# Y-babies_ATtiny84_v06.net
KiCad netlist of a schematic drawn in EAGLE
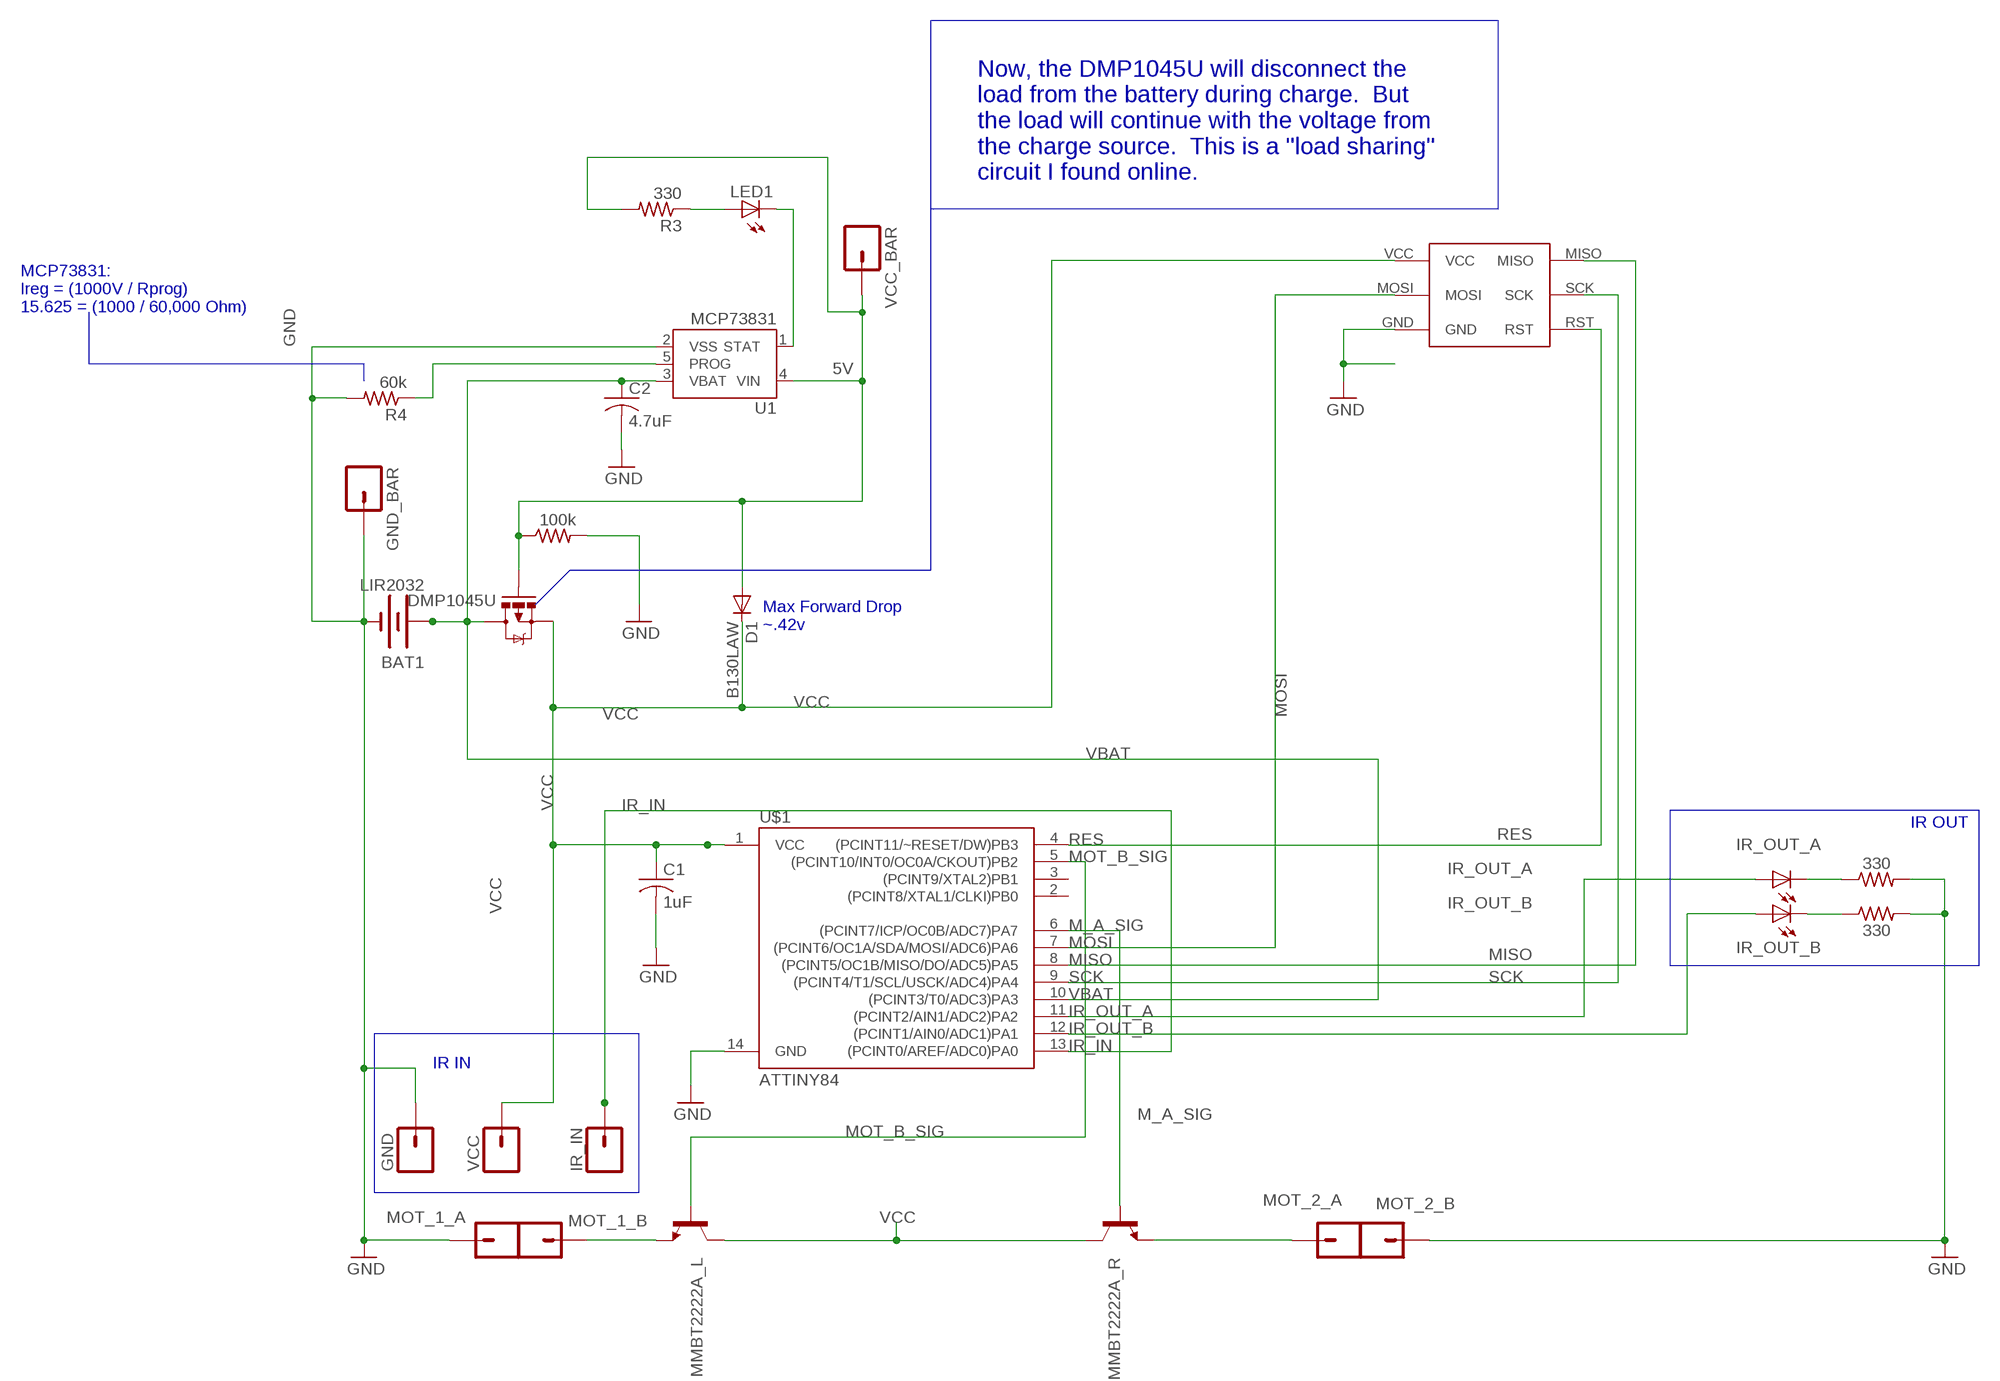
[diagram p0: schematic, sheet 1]

(export (version "E")
  (design (tool "Eeschema 10.0.6"))
  (components
    (comp (ref "BAT1")
      (value "LIR2032")
      (footprint "eagle-import:BATTCOM_20MM_PTH")
      (libsource (lib "eagle-import") (part "BATTERY20PTH"))
    )
    (comp (ref "C1")
      (value "1uF")
      (footprint "eagle-import:C0402K")
      (libsource (lib "eagle-import") (part "C-USC0402K"))
    )
    (comp (ref "C2")
      (value "4.7uF")
      (footprint "eagle-import:C0805K")
      (libsource (lib "eagle-import") (part "C-USC0805K"))
    )
    (comp (ref "D1")
      (value "B130LAW")
      (footprint "eagle-import:SOD123")
      (libsource (lib "eagle-import") (part "DIODE-SOD123"))
    )
    (comp (ref "DMP1045U")
      (value "MOSFET-PCHANNELSMD")
      (footprint "eagle-import:SOT23-3")
      (libsource (lib "eagle-import") (part "MOSFET-PCHANNELSMD"))
    )
    (comp (ref "GND")
      (value "M01PTH")
      (footprint "eagle-import:1X01")
      (libsource (lib "eagle-import") (part "M01PTH"))
    )
    (comp (ref "GND_BAR")
      (value "M01PTH")
      (footprint "eagle-import:1X01")
      (libsource (lib "eagle-import") (part "M01PTH"))
    )
    (comp (ref "IR_IN")
      (value "M01PTH")
      (footprint "eagle-import:1X01")
      (libsource (lib "eagle-import") (part "M01PTH"))
    )
    (comp (ref "IR_OUT_A")
      (value "LED3MM")
      (footprint "eagle-import:LED3MM")
      (libsource (lib "eagle-import") (part "LED3MM"))
    )
    (comp (ref "IR_OUT_B")
      (value "LED3MM")
      (footprint "eagle-import:LED3MM")
      (libsource (lib "eagle-import") (part "LED3MM"))
    )
    (comp (ref "LED1")
      (value "LEDSML0603")
      (footprint "eagle-import:SML0603")
      (libsource (lib "eagle-import") (part "LEDSML0603"))
    )
    (comp (ref "MMBT2222A_L")
      (value "TRANSISTOR_NPNSOT23")
      (footprint "eagle-import:SOT23")
      (libsource (lib "eagle-import") (part "TRANSISTOR_NPNSOT23"))
    )
    (comp (ref "MMBT2222A_R")
      (value "TRANSISTOR_NPNSOT23")
      (footprint "eagle-import:SOT23")
      (libsource (lib "eagle-import") (part "TRANSISTOR_NPNSOT23"))
    )
    (comp (ref "MOT_1_A")
      (value "M01SMD-4.5X1.5")
      (footprint "eagle-import:PAD-1.5X4.5")
      (libsource (lib "eagle-import") (part "M01SMD-4.5X1.5"))
    )
    (comp (ref "MOT_1_B")
      (value "M01SMD-4.5X1.5")
      (footprint "eagle-import:PAD-1.5X4.5")
      (libsource (lib "eagle-import") (part "M01SMD-4.5X1.5"))
    )
    (comp (ref "MOT_2_A")
      (value "M01SMD-4.5X1.5")
      (footprint "eagle-import:PAD-1.5X4.5")
      (libsource (lib "eagle-import") (part "M01SMD-4.5X1.5"))
    )
    (comp (ref "MOT_2_B")
      (value "M01SMD-4.5X1.5")
      (footprint "eagle-import:PAD-1.5X4.5")
      (libsource (lib "eagle-import") (part "M01SMD-4.5X1.5"))
    )
    (comp (ref "R1")
      (value "330")
      (footprint "eagle-import:R0402")
      (libsource (lib "eagle-import") (part "R-US_R0402"))
    )
    (comp (ref "R2")
      (value "330")
      (footprint "eagle-import:R0402")
      (libsource (lib "eagle-import") (part "R-US_R0402"))
    )
    (comp (ref "R3")
      (value "330")
      (footprint "eagle-import:R0402")
      (libsource (lib "eagle-import") (part "R-US_R0402"))
    )
    (comp (ref "R4")
      (value "60k")
      (footprint "eagle-import:R0402")
      (libsource (lib "eagle-import") (part "R-US_R0402"))
    )
    (comp (ref "R5")
      (value "100k")
      (footprint "eagle-import:R0402")
      (libsource (lib "eagle-import") (part "R-US_R0402"))
    )
    (comp (ref "U$1")
      (value "ATTINY84")
      (footprint "eagle-import:SO14")
      (libsource (lib "eagle-import") (part "ATTINY84"))
    )
    (comp (ref "U$2")
      (value "POGO_PIN_SPI_PAD")
      (footprint "eagle-import:POGO_PIN_SPI_PAD")
      (libsource (lib "eagle-import") (part "POGO_PIN_SPI_PAD"))
    )
    (comp (ref "U1")
      (value "MCP73831")
      (footprint "eagle-import:SOT23-5")
      (libsource (lib "eagle-import") (part "MCP73831"))
    )
    (comp (ref "VCC")
      (value "M01PTH")
      (footprint "eagle-import:1X01")
      (libsource (lib "eagle-import") (part "M01PTH"))
    )
    (comp (ref "VCC_BAR")
      (value "M01PTH")
      (footprint "eagle-import:1X01")
      (libsource (lib "eagle-import") (part "M01PTH"))
    )
  )
  (nets
    (net (code "1") (name "/5V") (class "Default")
      (node (ref "D1") (pin "A") (pinfunction "A_A") (pintype "passive"))
      (node (ref "DMP1045U") (pin "1") (pinfunction "G_1") (pintype "passive"))
      (node (ref "R3") (pin "2") (pinfunction "2_2") (pintype "passive"))
      (node (ref "R5") (pin "1") (pinfunction "1_1") (pintype "passive"))
      (node (ref "U1") (pin "4") (pinfunction "VIN_4") (pintype "power_in"))
      (node (ref "VCC_BAR") (pin "1") (pinfunction "1_1") (pintype "passive"))
    )
    (net (code "2") (name "/IR_IN") (class "Default")
      (node (ref "IR_IN") (pin "1") (pinfunction "1_1") (pintype "passive"))
      (node (ref "U$1") (pin "13") (pinfunction "(PCINT0/AREF/ADC0)PA0_13") (pintype "bidirectional"))
    )
    (net (code "3") (name "/IR_OUT_A") (class "Default")
      (node (ref "IR_OUT_A") (pin "A") (pinfunction "A_A") (pintype "passive"))
      (node (ref "U$1") (pin "11") (pinfunction "(PCINT2/AIN1/ADC2)PA2_11") (pintype "bidirectional"))
    )
    (net (code "4") (name "/IR_OUT_B") (class "Default")
      (node (ref "IR_OUT_B") (pin "A") (pinfunction "A_A") (pintype "passive"))
      (node (ref "U$1") (pin "12") (pinfunction "(PCINT1/AIN0/ADC1)PA1_12") (pintype "bidirectional"))
    )
    (net (code "5") (name "/MISO") (class "Default")
      (node (ref "U$1") (pin "8") (pinfunction "(PCINT5/OC1B/MISO/DO/ADC5)PA5_8") (pintype "bidirectional"))
      (node (ref "U$2") (pin "MISO") (pinfunction "MISO_MISO") (pintype "bidirectional"))
    )
    (net (code "6") (name "/MOSI") (class "Default")
      (node (ref "U$1") (pin "7") (pinfunction "(PCINT6/OC1A/SDA/MOSI/ADC6)PA6_7") (pintype "bidirectional"))
      (node (ref "U$2") (pin "MOSI") (pinfunction "MOSI_MOSI") (pintype "bidirectional"))
    )
    (net (code "7") (name "/MOT_B_SIG") (class "Default")
      (node (ref "MMBT2222A_L") (pin "1") (pinfunction "B_1") (pintype "passive"))
      (node (ref "U$1") (pin "5") (pinfunction "(PCINT10/INT0/OC0A/CKOUT)PB2_5") (pintype "bidirectional"))
    )
    (net (code "8") (name "/M_A_SIG") (class "Default")
      (node (ref "MMBT2222A_R") (pin "1") (pinfunction "B_1") (pintype "passive"))
      (node (ref "U$1") (pin "6") (pinfunction "(PCINT7/ICP/OC0B/ADC7)PA7_6") (pintype "bidirectional"))
    )
    (net (code "9") (name "/RES") (class "Default")
      (node (ref "U$1") (pin "4") (pinfunction "(PCINT11/~{RESET/DW})PB3_4") (pintype "bidirectional"))
      (node (ref "U$2") (pin "RST") (pinfunction "RST_RST") (pintype "bidirectional"))
    )
    (net (code "10") (name "/SCK") (class "Default")
      (node (ref "U$1") (pin "9") (pinfunction "(PCINT4/T1/SCL/USCK/ADC4)PA4_9") (pintype "bidirectional"))
      (node (ref "U$2") (pin "SCK") (pinfunction "SCK_SCK") (pintype "bidirectional"))
    )
    (net (code "11") (name "/VBAT") (class "Default")
      (node (ref "BAT1") (pin "1") (pinfunction "+_1") (pintype "power_in"))
      (node (ref "C2") (pin "1") (pinfunction "1_1") (pintype "passive"))
      (node (ref "DMP1045U") (pin "3") (pinfunction "D_3") (pintype "passive"))
      (node (ref "U$1") (pin "10") (pinfunction "(PCINT3/T0/ADC3)PA3_10") (pintype "bidirectional"))
      (node (ref "U1") (pin "3") (pinfunction "VBAT_3") (pintype "power_in"))
    )
    (net (code "12") (name "/VCC") (class "Default")
      (node (ref "C1") (pin "1") (pinfunction "1_1") (pintype "passive"))
      (node (ref "D1") (pin "C") (pinfunction "C_C") (pintype "passive"))
      (node (ref "DMP1045U") (pin "2") (pinfunction "S_2") (pintype "passive"))
      (node (ref "MMBT2222A_L") (pin "3") (pinfunction "C_3") (pintype "passive"))
      (node (ref "MMBT2222A_R") (pin "3") (pinfunction "C_3") (pintype "passive"))
      (node (ref "U$1") (pin "1") (pinfunction "VCC_1") (pintype "bidirectional"))
      (node (ref "U$2") (pin "VCC") (pinfunction "VCC_VCC") (pintype "bidirectional"))
      (node (ref "VCC") (pin "1") (pinfunction "1_1") (pintype "passive"))
    )
    (net (code "13") (name "GND") (class "Default")
      (node (ref "BAT1") (pin "2") (pinfunction "-_2") (pintype "power_in"))
      (node (ref "C1") (pin "2") (pinfunction "2_2") (pintype "passive"))
      (node (ref "C2") (pin "2") (pinfunction "2_2") (pintype "passive"))
      (node (ref "GND") (pin "1") (pinfunction "1_1") (pintype "passive"))
      (node (ref "GND_BAR") (pin "1") (pinfunction "1_1") (pintype "passive"))
      (node (ref "MOT_1_A") (pin "P$1") (pinfunction "1_P$1") (pintype "passive"))
      (node (ref "MOT_2_B") (pin "P$1") (pinfunction "1_P$1") (pintype "passive"))
      (node (ref "R1") (pin "2") (pinfunction "2_2") (pintype "passive"))
      (node (ref "R2") (pin "2") (pinfunction "2_2") (pintype "passive"))
      (node (ref "R4") (pin "2") (pinfunction "2_2") (pintype "passive"))
      (node (ref "R5") (pin "2") (pinfunction "2_2") (pintype "passive"))
      (node (ref "U$1") (pin "14") (pinfunction "GND_14") (pintype "bidirectional"))
      (node (ref "U$2") (pin "GND") (pinfunction "GND_GND") (pintype "bidirectional"))
      (node (ref "U1") (pin "2") (pinfunction "VSS_2") (pintype "power_in"))
    )
    (net (code "14") (name "Net-(IR_OUT_A-C)") (class "Default")
      (node (ref "IR_OUT_A") (pin "K") (pinfunction "C_K") (pintype "passive"))
      (node (ref "R1") (pin "1") (pinfunction "1_1") (pintype "passive"))
    )
    (net (code "15") (name "Net-(IR_OUT_B-C)") (class "Default")
      (node (ref "IR_OUT_B") (pin "K") (pinfunction "C_K") (pintype "passive"))
      (node (ref "R2") (pin "1") (pinfunction "1_1") (pintype "passive"))
    )
    (net (code "16") (name "Net-(LED1-PadA)") (class "Default")
      (node (ref "LED1") (pin "A") (pinfunction "A_A") (pintype "passive"))
      (node (ref "R3") (pin "1") (pinfunction "1_1") (pintype "passive"))
    )
    (net (code "17") (name "Net-(MMBT2222A_L-E)") (class "Default")
      (node (ref "MMBT2222A_L") (pin "2") (pinfunction "E_2") (pintype "passive"))
      (node (ref "MOT_1_B") (pin "P$1") (pinfunction "1_P$1") (pintype "passive"))
    )
    (net (code "18") (name "Net-(MMBT2222A_R-E)") (class "Default")
      (node (ref "MMBT2222A_R") (pin "2") (pinfunction "E_2") (pintype "passive"))
      (node (ref "MOT_2_A") (pin "P$1") (pinfunction "1_P$1") (pintype "passive"))
    )
    (net (code "19") (name "Net-(U1-PROG)") (class "Default")
      (node (ref "R4") (pin "1") (pinfunction "1_1") (pintype "passive"))
      (node (ref "U1") (pin "5") (pinfunction "PROG_5") (pintype "input"))
    )
    (net (code "20") (name "Net-(U1-STAT)") (class "Default")
      (node (ref "LED1") (pin "C") (pinfunction "C_C") (pintype "passive"))
      (node (ref "U1") (pin "1") (pinfunction "STAT_1") (pintype "output"))
    )
    (net (code "21") (name "unconnected-(U$1-(PCINT8{slash}XTAL1{slash}CLKI)PB0-Pad2)") (class "Default")
      (node (ref "U$1") (pin "2") (pinfunction "(PCINT8/XTAL1/CLKI)PB0_2") (pintype "bidirectional"))
    )
    (net (code "22") (name "unconnected-(U$1-(PCINT9{slash}XTAL2)PB1-Pad3)") (class "Default")
      (node (ref "U$1") (pin "3") (pinfunction "(PCINT9/XTAL2)PB1_3") (pintype "bidirectional"))
    )
  )
)
